# EEZ_DIB_BP3C_r3B3.net
KiCad netlist of a schematic drawn in EAGLE
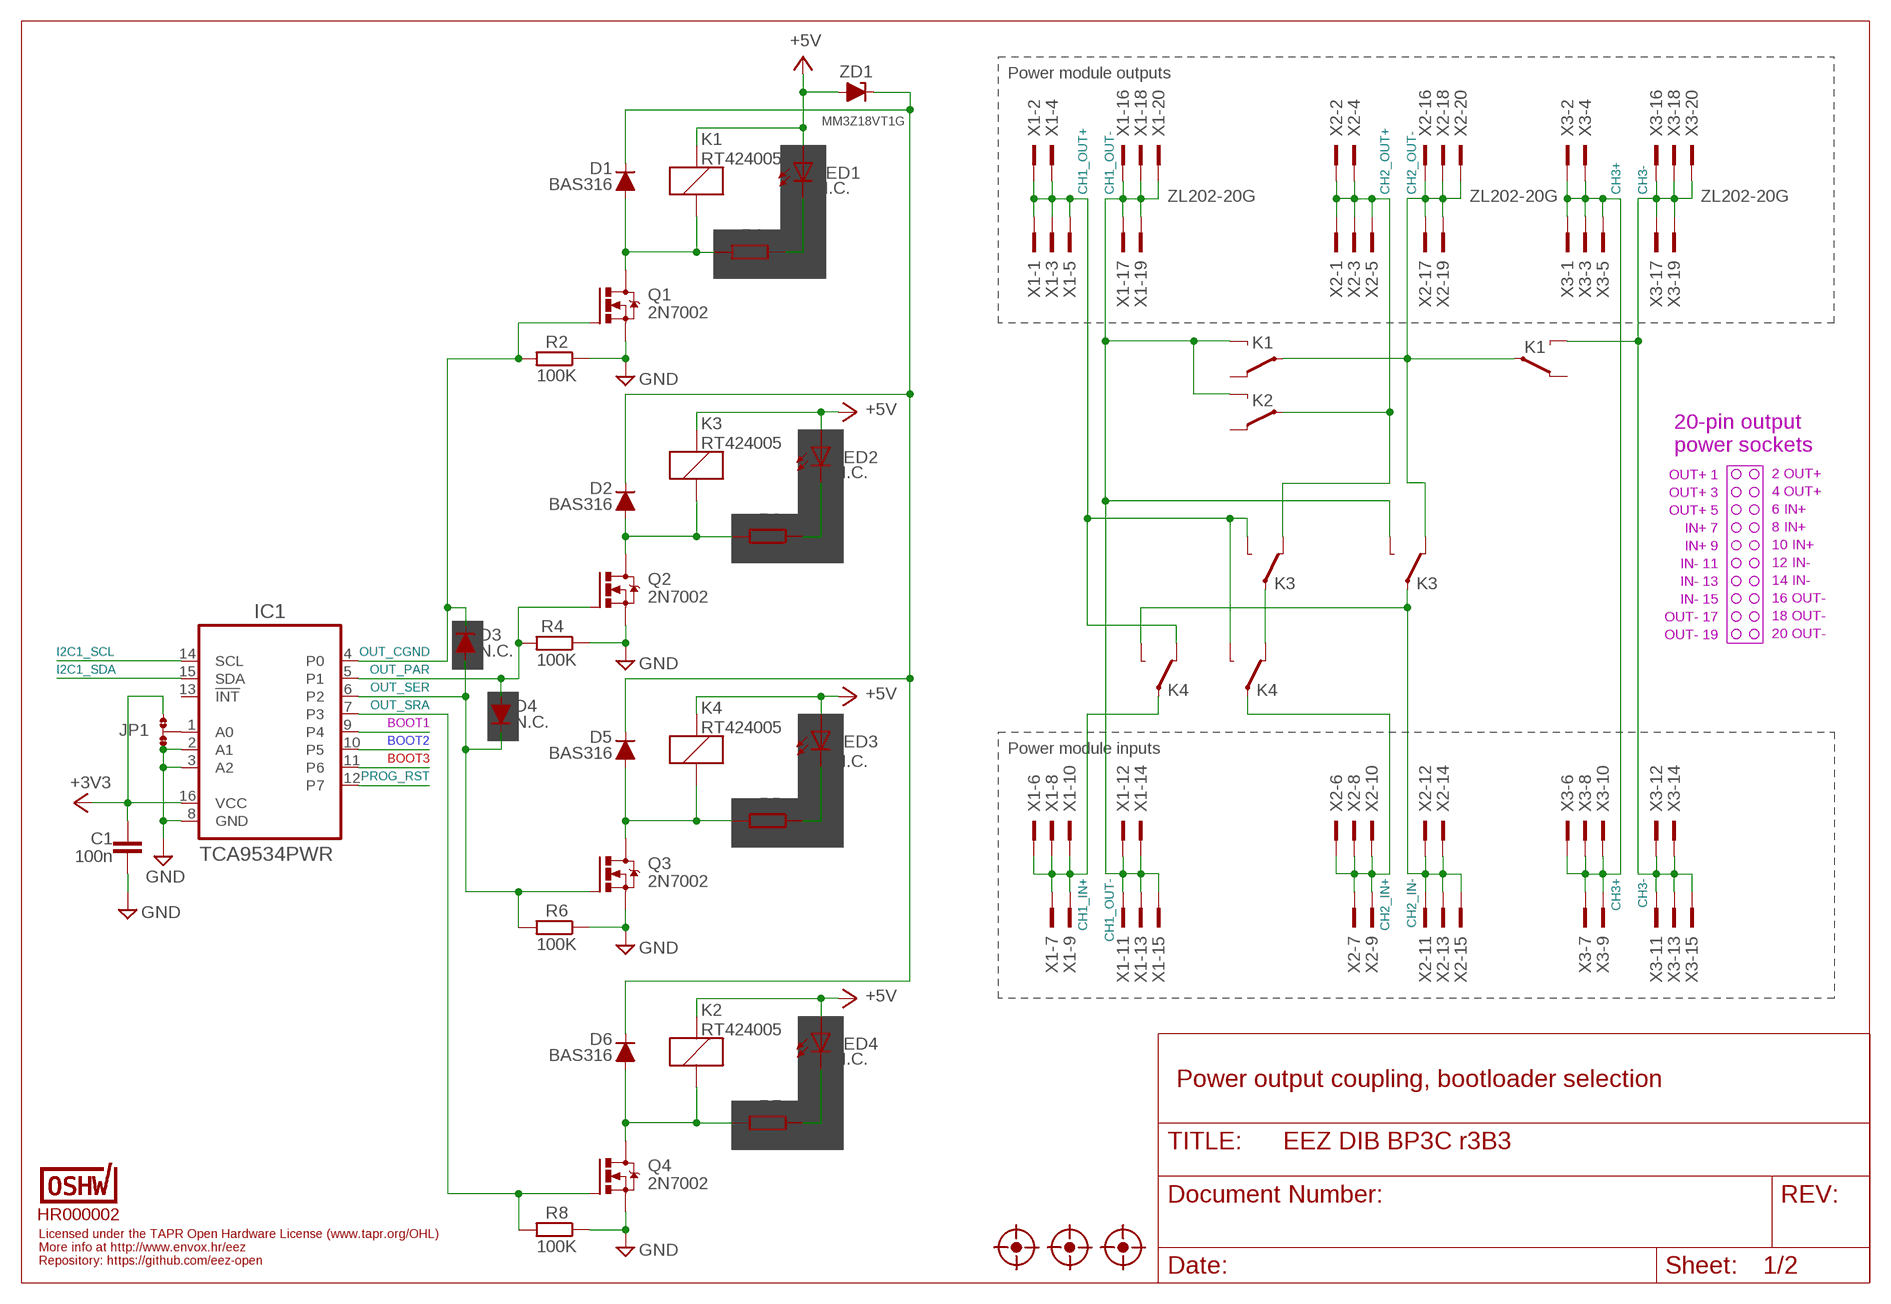
[diagram p0: schematic, sheet 1]
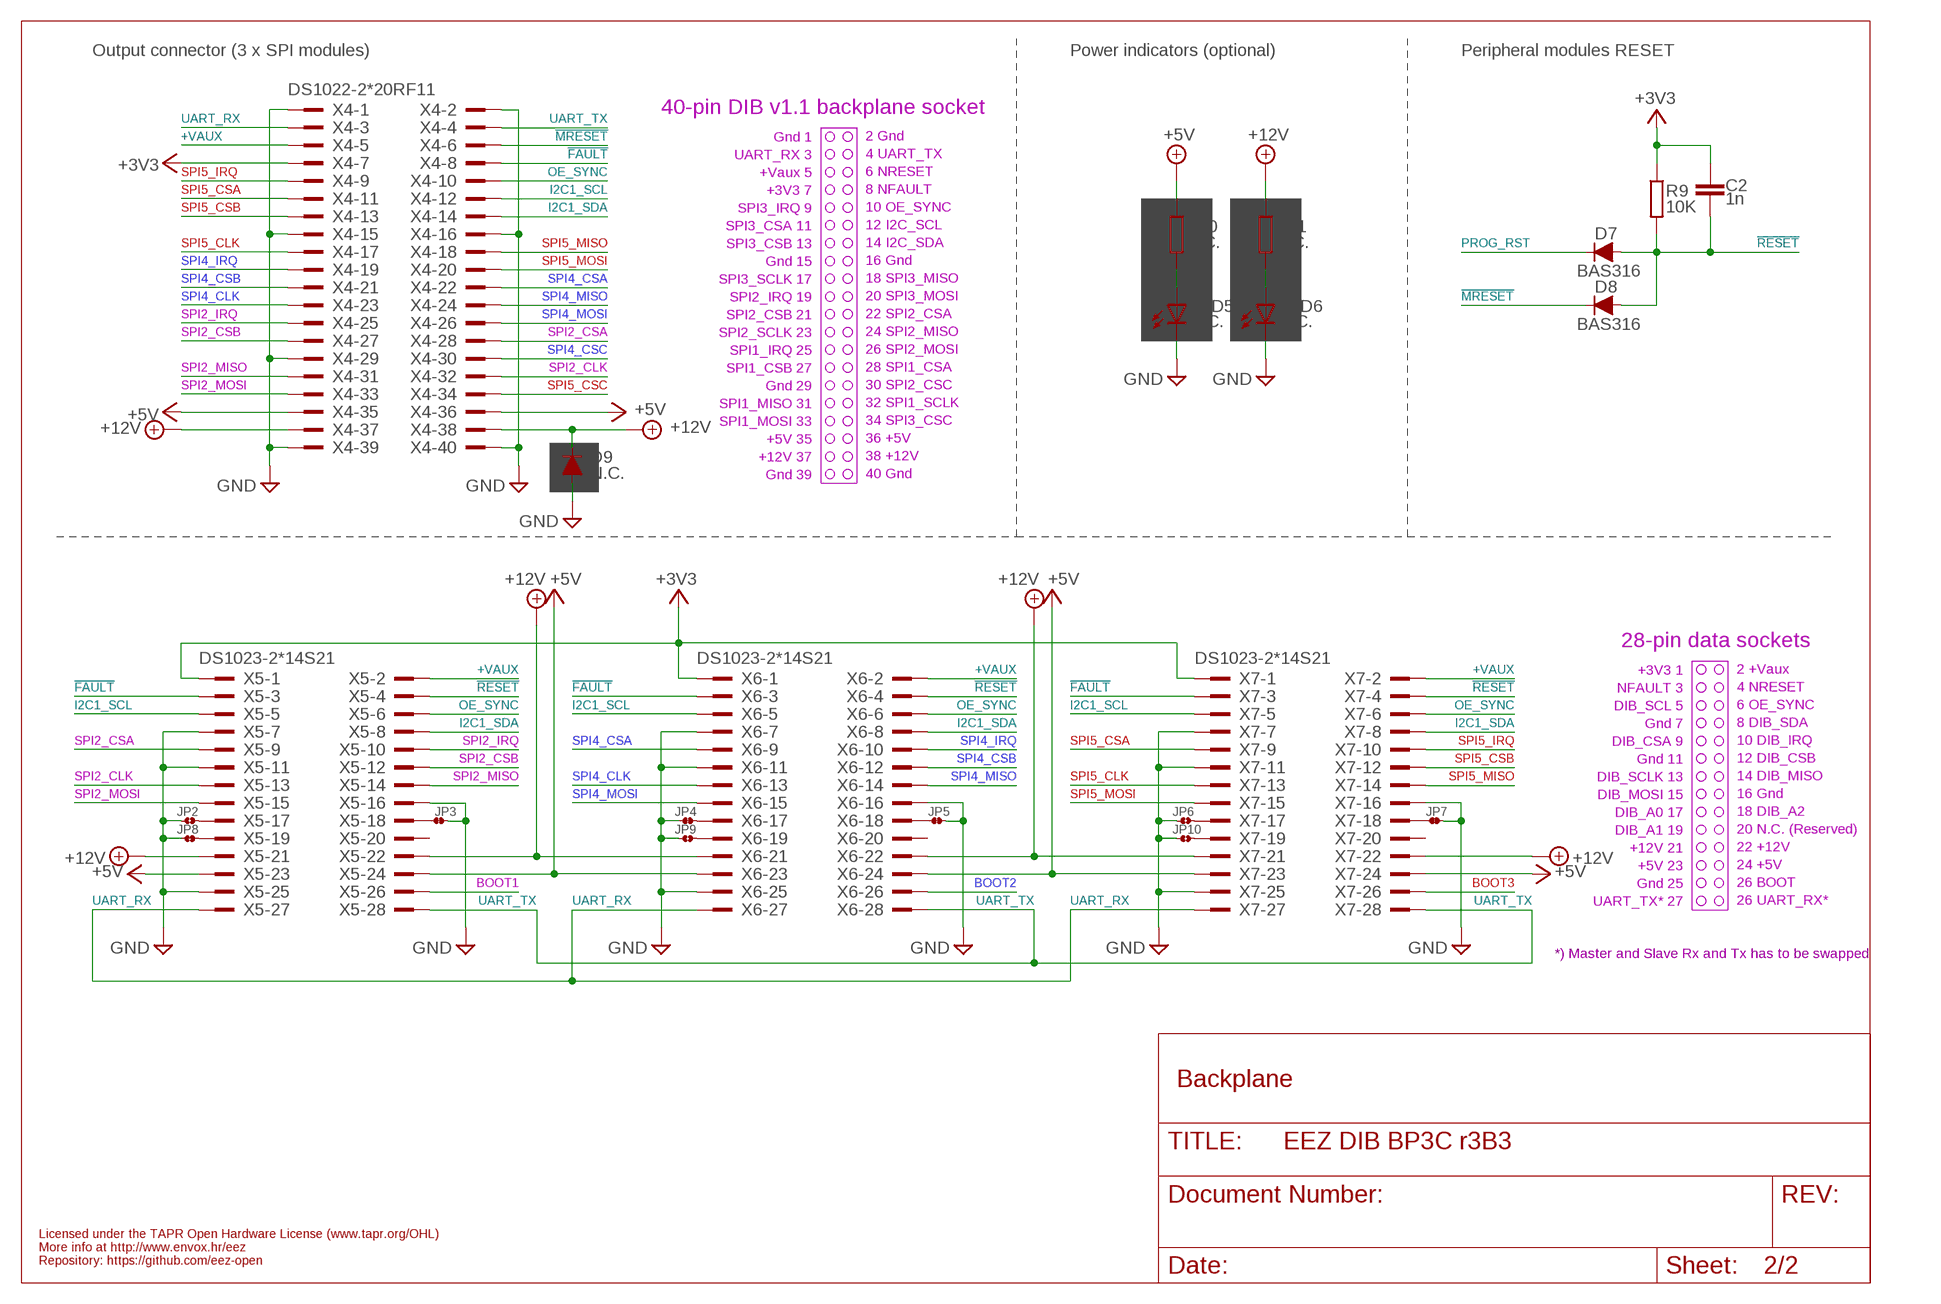
[diagram p1: schematic, sheet 2]

(export (version "E")
  (design (tool "Eeschema 10.0.6"))
  (components
    (comp (ref "C2")
      (value "1n")
      (footprint "eagle-import:C0805")
      (libsource (lib "eagle-import") (part "C-EUC0805"))
    )
    (comp (ref "D7")
      (value "BAS316")
      (footprint "eagle-import:SOD323-R")
      (libsource (lib "eagle-import") (part "DIODESOD323R"))
    )
    (comp (ref "D8")
      (value "BAS316")
      (footprint "eagle-import:SOD323-R")
      (libsource (lib "eagle-import") (part "DIODESOD323R"))
    )
    (comp (ref "D9")
      (value "N.C.")
      (footprint "eagle-import:DO214AA")
      (libsource (lib "eagle-import") (part "MyLib6_DIODEDO214AA"))
    )
    (comp (ref "JP2")
      (value "JP2-CUT")
      (footprint "eagle-import:JP2-CUT")
      (libsource (lib "eagle-import") (part "JP2-CUT"))
    )
    (comp (ref "JP3")
      (value "JP2-NOCUT")
      (footprint "eagle-import:JP2-NOCUT")
      (libsource (lib "eagle-import") (part "JP2-NOCUT"))
    )
    (comp (ref "JP4")
      (value "JP2-NOCUT")
      (footprint "eagle-import:JP2-NOCUT")
      (libsource (lib "eagle-import") (part "JP2-NOCUT"))
    )
    (comp (ref "JP5")
      (value "JP2-NOCUT")
      (footprint "eagle-import:JP2-NOCUT")
      (libsource (lib "eagle-import") (part "JP2-NOCUT"))
    )
    (comp (ref "JP6")
      (value "JP2-CUT")
      (footprint "eagle-import:JP2-CUT")
      (libsource (lib "eagle-import") (part "JP2-CUT"))
    )
    (comp (ref "JP7")
      (value "JP2-NOCUT")
      (footprint "eagle-import:JP2-NOCUT")
      (libsource (lib "eagle-import") (part "JP2-NOCUT"))
    )
    (comp (ref "JP8")
      (value "JP2-NOCUT")
      (footprint "eagle-import:JP2-NOCUT")
      (libsource (lib "eagle-import") (part "JP2-NOCUT"))
    )
    (comp (ref "JP9")
      (value "JP2-CUT")
      (footprint "eagle-import:JP2-CUT")
      (libsource (lib "eagle-import") (part "JP2-CUT"))
    )
    (comp (ref "JP10")
      (value "JP2-CUT")
      (footprint "eagle-import:JP2-CUT")
      (libsource (lib "eagle-import") (part "JP2-CUT"))
    )
    (comp (ref "LED5")
      (value "N.C.")
      (footprint "eagle-import:LED_0805")
      (libsource (lib "eagle-import") (part "LED0805"))
    )
    (comp (ref "LED6")
      (value "N.C.")
      (footprint "eagle-import:LED_0805")
      (libsource (lib "eagle-import") (part "LED0805"))
    )
    (comp (ref "R9")
      (value "10K")
      (footprint "eagle-import:R0805")
      (libsource (lib "eagle-import") (part "R-EU_R0805"))
    )
    (comp (ref "R10")
      (value "N.C.")
      (footprint "eagle-import:R0805")
      (libsource (lib "eagle-import") (part "R-EU_R0805"))
    )
    (comp (ref "R11")
      (value "N.C.")
      (footprint "eagle-import:R0805")
      (libsource (lib "eagle-import") (part "R-EU_R0805"))
    )
    (comp (ref "X4")
      (value "DS1022-2*20RF11")
      (footprint "eagle-import:ZL212-40KG")
      (libsource (lib "eagle-import") (part "ZL212-40KG"))
    )
    (comp (ref "X5")
      (value "DS1023-2*14S21")
      (footprint "eagle-import:TSW-114-07-F-D")
      (libsource (lib "eagle-import") (part "TSW-114-07-F-D"))
    )
    (comp (ref "X6")
      (value "DS1023-2*14S21")
      (footprint "eagle-import:TSW-114-07-F-D")
      (libsource (lib "eagle-import") (part "TSW-114-07-F-D"))
    )
    (comp (ref "X7")
      (value "DS1023-2*14S21")
      (footprint "eagle-import:TSW-114-07-F-D")
      (libsource (lib "eagle-import") (part "TSW-114-07-F-D"))
    )
    (comp (ref "C1")
      (value "100n")
      (footprint "eagle-import:C0603")
      (libsource (lib "eagle-import") (part "C-EUC0603"))
    )
    (comp (ref "D1")
      (value "BAS316")
      (footprint "eagle-import:SOD323-R")
      (libsource (lib "eagle-import") (part "DIODESOD323R"))
    )
    (comp (ref "D2")
      (value "BAS316")
      (footprint "eagle-import:SOD323-R")
      (libsource (lib "eagle-import") (part "DIODESOD323R"))
    )
    (comp (ref "D3")
      (value "N.C.")
      (footprint "eagle-import:SOD323-R")
      (libsource (lib "eagle-import") (part "DIODESOD323R"))
    )
    (comp (ref "D4")
      (value "N.C.")
      (footprint "eagle-import:SOD323-R")
      (libsource (lib "eagle-import") (part "DIODESOD323R"))
    )
    (comp (ref "D5")
      (value "BAS316")
      (footprint "eagle-import:SOD323-R")
      (libsource (lib "eagle-import") (part "DIODESOD323R"))
    )
    (comp (ref "D6")
      (value "BAS316")
      (footprint "eagle-import:SOD323-R")
      (libsource (lib "eagle-import") (part "DIODESOD323R"))
    )
    (comp (ref "FM1")
      (value "FIDUCIAL")
      (footprint "eagle-import:FIDUCIAL")
      (libsource (lib "eagle-import") (part "FIDUCIAL"))
    )
    (comp (ref "FM2")
      (value "FIDUCIAL")
      (footprint "eagle-import:FIDUCIAL")
      (libsource (lib "eagle-import") (part "FIDUCIAL"))
    )
    (comp (ref "FM3")
      (value "FIDUCIAL")
      (footprint "eagle-import:FIDUCIAL")
      (libsource (lib "eagle-import") (part "FIDUCIAL"))
    )
    (comp (ref "IC1")
      (value "TCA9534PWR")
      (footprint "eagle-import:PW(R-PDSO-G16)")
      (libsource (lib "eagle-import") (part "TCA9534PWR"))
    )
    (comp (ref "JP1")
      (value "JP3-CUT")
      (footprint "eagle-import:JP3-CUT")
      (libsource (lib "eagle-import") (part "JP3-CUT"))
    )
    (comp (ref "K1")
      (value "RT424005")
      (footprint "eagle-import:RT-C_016A5_ROUND")
      (libsource (lib "eagle-import") (part "RELAY_RT314012-2"))
    )
    (comp (ref "K2")
      (value "RT424005")
      (footprint "eagle-import:RT-C_016A5_ROUND")
      (libsource (lib "eagle-import") (part "RELAY_RT314012-2"))
    )
    (comp (ref "K3")
      (value "RT424005")
      (footprint "eagle-import:RT-C_016A5_ROUND")
      (libsource (lib "eagle-import") (part "RELAY_RT314012-2"))
    )
    (comp (ref "K4")
      (value "RT424005")
      (footprint "eagle-import:RT-C_016A5_ROUND")
      (libsource (lib "eagle-import") (part "RELAY_RT314012-2"))
    )
    (comp (ref "LABEL1")
      (value "HR000002")
      (footprint "eagle-import:CERT-SMALL-SILK")
      (libsource (lib "eagle-import") (part "OSHWA-CERT-SMALL"))
    )
    (comp (ref "LED1")
      (value "N.C.")
      (footprint "eagle-import:LED_0805")
      (libsource (lib "eagle-import") (part "LED0805"))
    )
    (comp (ref "LED2")
      (value "N.C.")
      (footprint "eagle-import:LED_0805")
      (libsource (lib "eagle-import") (part "LED0805"))
    )
    (comp (ref "LED3")
      (value "N.C.")
      (footprint "eagle-import:LED_0805")
      (libsource (lib "eagle-import") (part "LED0805"))
    )
    (comp (ref "LED4")
      (value "N.C.")
      (footprint "eagle-import:LED_0805")
      (libsource (lib "eagle-import") (part "LED0805"))
    )
    (comp (ref "Q1")
      (value "2N7002")
      (footprint "eagle-import:SOT103P240X110-3N")
      (fields
        (field (name "MPN") "2N7002-7-F")
        (field (name "MPN_1") "2N7002-7-F")
        (field (name "OC_FARNELL") "1713823")
        (field (name "OC_NEWARK") "25R5679")
        (field (name "PACKAGE") "SOT-23-3")
        (field (name "SUPPLIER") "DIODES INC.")
      )
      (libsource (lib "eagle-import") (part "2N7002"))
    )
    (comp (ref "Q2")
      (value "2N7002")
      (footprint "eagle-import:SOT103P240X110-3N")
      (fields
        (field (name "MPN") "2N7002-7-F")
        (field (name "MPN_1") "2N7002-7-F")
        (field (name "OC_FARNELL") "1713823")
        (field (name "OC_NEWARK") "25R5679")
        (field (name "PACKAGE") "SOT-23-3")
        (field (name "SUPPLIER") "DIODES INC.")
      )
      (libsource (lib "eagle-import") (part "2N7002"))
    )
    (comp (ref "Q3")
      (value "2N7002")
      (footprint "eagle-import:SOT103P240X110-3N")
      (fields
        (field (name "MPN") "2N7002-7-F")
        (field (name "MPN_1") "2N7002-7-F")
        (field (name "OC_FARNELL") "1713823")
        (field (name "OC_NEWARK") "25R5679")
        (field (name "PACKAGE") "SOT-23-3")
        (field (name "SUPPLIER") "DIODES INC.")
      )
      (libsource (lib "eagle-import") (part "2N7002"))
    )
    (comp (ref "Q4")
      (value "2N7002")
      (footprint "eagle-import:SOT103P240X110-3N")
      (fields
        (field (name "MPN") "2N7002-7-F")
        (field (name "MPN_1") "2N7002-7-F")
        (field (name "OC_FARNELL") "1713823")
        (field (name "OC_NEWARK") "25R5679")
        (field (name "PACKAGE") "SOT-23-3")
        (field (name "SUPPLIER") "DIODES INC.")
      )
      (libsource (lib "eagle-import") (part "2N7002"))
    )
    (comp (ref "R1")
      (value "N.C.")
      (footprint "eagle-import:R0805")
      (libsource (lib "eagle-import") (part "R-EU_R0805"))
    )
    (comp (ref "R2")
      (value "100K")
      (footprint "eagle-import:R0805")
      (libsource (lib "eagle-import") (part "R-EU_R0805"))
    )
    (comp (ref "R3")
      (value "N.C.")
      (footprint "eagle-import:R0805")
      (libsource (lib "eagle-import") (part "R-EU_R0805"))
    )
    (comp (ref "R4")
      (value "100K")
      (footprint "eagle-import:R0805")
      (libsource (lib "eagle-import") (part "R-EU_R0805"))
    )
    (comp (ref "R5")
      (value "N.C.")
      (footprint "eagle-import:R0805")
      (libsource (lib "eagle-import") (part "R-EU_R0805"))
    )
    (comp (ref "R6")
      (value "100K")
      (footprint "eagle-import:R0805")
      (libsource (lib "eagle-import") (part "R-EU_R0805"))
    )
    (comp (ref "R7")
      (value "N.C.")
      (footprint "eagle-import:R0805")
      (libsource (lib "eagle-import") (part "R-EU_R0805"))
    )
    (comp (ref "R8")
      (value "100K")
      (footprint "eagle-import:R0805")
      (libsource (lib "eagle-import") (part "R-EU_R0805"))
    )
    (comp (ref "X1")
      (value "ZL202-20G")
      (footprint "eagle-import:DS1021-2_10SF11")
      (libsource (lib "eagle-import") (part "DS1021-210SF11"))
    )
    (comp (ref "X2")
      (value "ZL202-20G")
      (footprint "eagle-import:DS1021-2_10SF11")
      (libsource (lib "eagle-import") (part "DS1021-210SF11"))
    )
    (comp (ref "X3")
      (value "ZL202-20G")
      (footprint "eagle-import:DS1021-2_10SF11")
      (libsource (lib "eagle-import") (part "DS1021-210SF11"))
    )
    (comp (ref "ZD1")
      (value "MM3Z18VT1G")
      (footprint "eagle-import:SOD323-R")
      (libsource (lib "eagle-import") (part "ZENER-DIODESOD323R"))
    )
  )
  (nets
    (net (code "1") (name "+3V3") (class "Default")
      (node (ref "C1") (pin "1") (pinfunction "1_1") (pintype "passive"))
      (node (ref "C2") (pin "2") (pinfunction "2_2") (pintype "passive"))
      (node (ref "IC1") (pin "16") (pinfunction "VCC_16") (pintype "passive"))
      (node (ref "JP1") (pin "NO") (pinfunction "NO_NO") (pintype "passive"))
      (node (ref "R9") (pin "1") (pinfunction "1_1") (pintype "passive"))
      (node (ref "X4") (pin "7") (pinfunction "1_7") (pintype "passive"))
      (node (ref "X5") (pin "1") (pinfunction "1_1") (pintype "passive"))
      (node (ref "X6") (pin "1") (pinfunction "1_1") (pintype "passive"))
      (node (ref "X7") (pin "1") (pinfunction "1_1") (pintype "passive"))
    )
    (net (code "2") (name "+5V") (class "Default")
      (node (ref "K1") (pin "A2") (pinfunction "C1_A2") (pintype "passive"))
      (node (ref "K2") (pin "A2") (pinfunction "C1_A2") (pintype "passive"))
      (node (ref "K3") (pin "A2") (pinfunction "C1_A2") (pintype "passive"))
      (node (ref "K4") (pin "A2") (pinfunction "C1_A2") (pintype "passive"))
      (node (ref "LED1") (pin "A") (pinfunction "A_A") (pintype "passive"))
      (node (ref "LED2") (pin "A") (pinfunction "A_A") (pintype "passive"))
      (node (ref "LED3") (pin "A") (pinfunction "A_A") (pintype "passive"))
      (node (ref "LED4") (pin "A") (pinfunction "A_A") (pintype "passive"))
      (node (ref "R10") (pin "1") (pinfunction "1_1") (pintype "passive"))
      (node (ref "X4") (pin "35") (pinfunction "1_35") (pintype "passive"))
      (node (ref "X4") (pin "36") (pinfunction "1_36") (pintype "passive"))
      (node (ref "X5") (pin "23") (pinfunction "1_23") (pintype "passive"))
      (node (ref "X5") (pin "24") (pinfunction "1_24") (pintype "passive"))
      (node (ref "X6") (pin "23") (pinfunction "1_23") (pintype "passive"))
      (node (ref "X6") (pin "24") (pinfunction "1_24") (pintype "passive"))
      (node (ref "X7") (pin "23") (pinfunction "1_23") (pintype "passive"))
      (node (ref "X7") (pin "24") (pinfunction "1_24") (pintype "passive"))
      (node (ref "ZD1") (pin "A") (pinfunction "A_A") (pintype "passive"))
    )
    (net (code "3") (name "+12V") (class "Default")
      (node (ref "D9") (pin "C") (pinfunction "C_C") (pintype "passive"))
      (node (ref "R11") (pin "1") (pinfunction "1_1") (pintype "passive"))
      (node (ref "X4") (pin "37") (pinfunction "1_37") (pintype "passive"))
      (node (ref "X4") (pin "38") (pinfunction "1_38") (pintype "passive"))
      (node (ref "X5") (pin "21") (pinfunction "1_21") (pintype "passive"))
      (node (ref "X5") (pin "22") (pinfunction "1_22") (pintype "passive"))
      (node (ref "X6") (pin "21") (pinfunction "1_21") (pintype "passive"))
      (node (ref "X6") (pin "22") (pinfunction "1_22") (pintype "passive"))
      (node (ref "X7") (pin "21") (pinfunction "1_21") (pintype "passive"))
      (node (ref "X7") (pin "22") (pinfunction "1_22") (pintype "passive"))
    )
    (net (code "4") (name "+VAUX") (class "Default")
      (node (ref "X4") (pin "5") (pinfunction "1_5") (pintype "passive"))
      (node (ref "X5") (pin "2") (pinfunction "1_2") (pintype "passive"))
      (node (ref "X6") (pin "2") (pinfunction "1_2") (pintype "passive"))
      (node (ref "X7") (pin "2") (pinfunction "1_2") (pintype "passive"))
    )
    (net (code "5") (name "BOOT1") (class "Default")
      (node (ref "IC1") (pin "9") (pinfunction "P4_9") (pintype "bidirectional"))
      (node (ref "X5") (pin "26") (pinfunction "1_26") (pintype "passive"))
    )
    (net (code "6") (name "BOOT2") (class "Default")
      (node (ref "IC1") (pin "10") (pinfunction "P5_10") (pintype "bidirectional"))
      (node (ref "X6") (pin "26") (pinfunction "1_26") (pintype "passive"))
    )
    (net (code "7") (name "BOOT3") (class "Default")
      (node (ref "IC1") (pin "11") (pinfunction "P6_11") (pintype "bidirectional"))
      (node (ref "X7") (pin "26") (pinfunction "1_26") (pintype "passive"))
    )
    (net (code "8") (name "CH1_IN+") (class "Default")
      (node (ref "K4") (pin "11A") (pinfunction "P_11A") (pintype "passive"))
      (node (ref "X1") (pin "10") (pinfunction "1_10") (pintype "passive"))
      (node (ref "X1") (pin "6") (pinfunction "1_6") (pintype "passive"))
      (node (ref "X1") (pin "7") (pinfunction "1_7") (pintype "passive"))
      (node (ref "X1") (pin "8") (pinfunction "1_8") (pintype "passive"))
      (node (ref "X1") (pin "9") (pinfunction "1_9") (pintype "passive"))
    )
    (net (code "9") (name "CH1_OUT+") (class "Default")
      (node (ref "K3") (pin "14A") (pinfunction "O_14A") (pintype "passive"))
      (node (ref "K4") (pin "12A") (pinfunction "S_12A") (pintype "passive"))
      (node (ref "K4") (pin "14B") (pinfunction "O_14B") (pintype "passive"))
      (node (ref "X1") (pin "1") (pinfunction "1_1") (pintype "passive"))
      (node (ref "X1") (pin "2") (pinfunction "1_2") (pintype "passive"))
      (node (ref "X1") (pin "3") (pinfunction "1_3") (pintype "passive"))
      (node (ref "X1") (pin "4") (pinfunction "1_4") (pintype "passive"))
      (node (ref "X1") (pin "5") (pinfunction "1_5") (pintype "passive"))
    )
    (net (code "10") (name "CH1_OUT-") (class "Default")
      (node (ref "K1") (pin "14A") (pinfunction "O_14A") (pintype "passive"))
      (node (ref "K2") (pin "14A") (pinfunction "O_14A") (pintype "passive"))
      (node (ref "K3") (pin "14B") (pinfunction "O_14B") (pintype "passive"))
      (node (ref "X1") (pin "11") (pinfunction "1_11") (pintype "passive"))
      (node (ref "X1") (pin "12") (pinfunction "1_12") (pintype "passive"))
      (node (ref "X1") (pin "13") (pinfunction "1_13") (pintype "passive"))
      (node (ref "X1") (pin "14") (pinfunction "1_14") (pintype "passive"))
      (node (ref "X1") (pin "15") (pinfunction "1_15") (pintype "passive"))
      (node (ref "X1") (pin "16") (pinfunction "1_16") (pintype "passive"))
      (node (ref "X1") (pin "17") (pinfunction "1_17") (pintype "passive"))
      (node (ref "X1") (pin "18") (pinfunction "1_18") (pintype "passive"))
      (node (ref "X1") (pin "19") (pinfunction "1_19") (pintype "passive"))
      (node (ref "X1") (pin "20") (pinfunction "1_20") (pintype "passive"))
    )
    (net (code "11") (name "CH2_IN+") (class "Default")
      (node (ref "K4") (pin "11B") (pinfunction "P_11B") (pintype "passive"))
      (node (ref "X2") (pin "10") (pinfunction "1_10") (pintype "passive"))
      (node (ref "X2") (pin "6") (pinfunction "1_6") (pintype "passive"))
      (node (ref "X2") (pin "7") (pinfunction "1_7") (pintype "passive"))
      (node (ref "X2") (pin "8") (pinfunction "1_8") (pintype "passive"))
      (node (ref "X2") (pin "9") (pinfunction "1_9") (pintype "passive"))
    )
    (net (code "12") (name "CH2_IN-") (class "Default")
      (node (ref "K3") (pin "11B") (pinfunction "P_11B") (pintype "passive"))
      (node (ref "K4") (pin "14A") (pinfunction "O_14A") (pintype "passive"))
      (node (ref "X2") (pin "11") (pinfunction "1_11") (pintype "passive"))
      (node (ref "X2") (pin "12") (pinfunction "1_12") (pintype "passive"))
      (node (ref "X2") (pin "13") (pinfunction "1_13") (pintype "passive"))
      (node (ref "X2") (pin "14") (pinfunction "1_14") (pintype "passive"))
      (node (ref "X2") (pin "15") (pinfunction "1_15") (pintype "passive"))
    )
    (net (code "13") (name "CH2_OUT+") (class "Default")
      (node (ref "K2") (pin "11A") (pinfunction "P_11A") (pintype "passive"))
      (node (ref "K3") (pin "12A") (pinfunction "S_12A") (pintype "passive"))
      (node (ref "X2") (pin "1") (pinfunction "1_1") (pintype "passive"))
      (node (ref "X2") (pin "2") (pinfunction "1_2") (pintype "passive"))
      (node (ref "X2") (pin "3") (pinfunction "1_3") (pintype "passive"))
      (node (ref "X2") (pin "4") (pinfunction "1_4") (pintype "passive"))
      (node (ref "X2") (pin "5") (pinfunction "1_5") (pintype "passive"))
    )
    (net (code "14") (name "CH2_OUT-") (class "Default")
      (node (ref "K1") (pin "11A") (pinfunction "P_11A") (pintype "passive"))
      (node (ref "K1") (pin "11B") (pinfunction "P_11B") (pintype "passive"))
      (node (ref "K3") (pin "12B") (pinfunction "S_12B") (pintype "passive"))
      (node (ref "X2") (pin "16") (pinfunction "1_16") (pintype "passive"))
      (node (ref "X2") (pin "17") (pinfunction "1_17") (pintype "passive"))
      (node (ref "X2") (pin "18") (pinfunction "1_18") (pintype "passive"))
      (node (ref "X2") (pin "19") (pinfunction "1_19") (pintype "passive"))
      (node (ref "X2") (pin "20") (pinfunction "1_20") (pintype "passive"))
    )
    (net (code "15") (name "CH3+") (class "Default")
      (node (ref "X3") (pin "1") (pinfunction "1_1") (pintype "passive"))
      (node (ref "X3") (pin "10") (pinfunction "1_10") (pintype "passive"))
      (node (ref "X3") (pin "2") (pinfunction "1_2") (pintype "passive"))
      (node (ref "X3") (pin "3") (pinfunction "1_3") (pintype "passive"))
      (node (ref "X3") (pin "4") (pinfunction "1_4") (pintype "passive"))
      (node (ref "X3") (pin "5") (pinfunction "1_5") (pintype "passive"))
      (node (ref "X3") (pin "6") (pinfunction "1_6") (pintype "passive"))
      (node (ref "X3") (pin "7") (pinfunction "1_7") (pintype "passive"))
      (node (ref "X3") (pin "8") (pinfunction "1_8") (pintype "passive"))
      (node (ref "X3") (pin "9") (pinfunction "1_9") (pintype "passive"))
    )
    (net (code "16") (name "CH3-") (class "Default")
      (node (ref "K1") (pin "14B") (pinfunction "O_14B") (pintype "passive"))
      (node (ref "X3") (pin "11") (pinfunction "1_11") (pintype "passive"))
      (node (ref "X3") (pin "12") (pinfunction "1_12") (pintype "passive"))
      (node (ref "X3") (pin "13") (pinfunction "1_13") (pintype "passive"))
      (node (ref "X3") (pin "14") (pinfunction "1_14") (pintype "passive"))
      (node (ref "X3") (pin "15") (pinfunction "1_15") (pintype "passive"))
      (node (ref "X3") (pin "16") (pinfunction "1_16") (pintype "passive"))
      (node (ref "X3") (pin "17") (pinfunction "1_17") (pintype "passive"))
      (node (ref "X3") (pin "18") (pinfunction "1_18") (pintype "passive"))
      (node (ref "X3") (pin "19") (pinfunction "1_19") (pintype "passive"))
      (node (ref "X3") (pin "20") (pinfunction "1_20") (pintype "passive"))
    )
    (net (code "17") (name "GND") (class "Default")
      (node (ref "C1") (pin "2") (pinfunction "2_2") (pintype "passive"))
      (node (ref "D9") (pin "A") (pinfunction "A_A") (pintype "passive"))
      (node (ref "IC1") (pin "2") (pinfunction "A1_2") (pintype "input"))
      (node (ref "IC1") (pin "3") (pinfunction "A2_3") (pintype "input"))
      (node (ref "IC1") (pin "8") (pinfunction "GND_8") (pintype "passive"))
      (node (ref "JP1") (pin "NC") (pinfunction "NC_NC") (pintype "passive"))
      (node (ref "JP10") (pin "1") (pinfunction "1_1") (pintype "passive"))
      (node (ref "JP2") (pin "1") (pinfunction "1_1") (pintype "passive"))
      (node (ref "JP3") (pin "2") (pinfunction "2_2") (pintype "passive"))
      (node (ref "JP4") (pin "1") (pinfunction "1_1") (pintype "passive"))
      (node (ref "JP5") (pin "2") (pinfunction "2_2") (pintype "passive"))
      (node (ref "JP6") (pin "1") (pinfunction "1_1") (pintype "passive"))
      (node (ref "JP7") (pin "2") (pinfunction "2_2") (pintype "passive"))
      (node (ref "JP8") (pin "1") (pinfunction "1_1") (pintype "passive"))
      (node (ref "JP9") (pin "1") (pinfunction "1_1") (pintype "passive"))
      (node (ref "LED5") (pin "C") (pinfunction "C_C") (pintype "passive"))
      (node (ref "LED6") (pin "C") (pinfunction "C_C") (pintype "passive"))
      (node (ref "Q1") (pin "2") (pinfunction "S_2") (pintype "passive"))
      (node (ref "Q2") (pin "2") (pinfunction "S_2") (pintype "passive"))
      (node (ref "Q3") (pin "2") (pinfunction "S_2") (pintype "passive"))
      (node (ref "Q4") (pin "2") (pinfunction "S_2") (pintype "passive"))
      (node (ref "R2") (pin "1") (pinfunction "1_1") (pintype "passive"))
      (node (ref "R4") (pin "1") (pinfunction "1_1") (pintype "passive"))
      (node (ref "R6") (pin "1") (pinfunction "1_1") (pintype "passive"))
      (node (ref "R8") (pin "1") (pinfunction "1_1") (pintype "passive"))
      (node (ref "X4") (pin "1") (pinfunction "1_1") (pintype "passive"))
      (node (ref "X4") (pin "15") (pinfunction "1_15") (pintype "passive"))
      (node (ref "X4") (pin "16") (pinfunction "1_16") (pintype "passive"))
      (node (ref "X4") (pin "2") (pinfunction "1_2") (pintype "passive"))
      (node (ref "X4") (pin "29") (pinfunction "1_29") (pintype "passive"))
      (node (ref "X4") (pin "39") (pinfunction "1_39") (pintype "passive"))
      (node (ref "X4") (pin "40") (pinfunction "1_40") (pintype "passive"))
      (node (ref "X5") (pin "11") (pinfunction "1_11") (pintype "passive"))
      (node (ref "X5") (pin "16") (pinfunction "1_16") (pintype "passive"))
      (node (ref "X5") (pin "25") (pinfunction "1_25") (pintype "passive"))
      (node (ref "X5") (pin "7") (pinfunction "1_7") (pintype "passive"))
      (node (ref "X6") (pin "11") (pinfunction "1_11") (pintype "passive"))
      (node (ref "X6") (pin "16") (pinfunction "1_16") (pintype "passive"))
      (node (ref "X6") (pin "25") (pinfunction "1_25") (pintype "passive"))
      (node (ref "X6") (pin "7") (pinfunction "1_7") (pintype "passive"))
      (node (ref "X7") (pin "11") (pinfunction "1_11") (pintype "passive"))
      (node (ref "X7") (pin "16") (pinfunction "1_16") (pintype "passive"))
      (node (ref "X7") (pin "25") (pinfunction "1_25") (pintype "passive"))
      (node (ref "X7") (pin "7") (pinfunction "1_7") (pintype "passive"))
    )
    (net (code "18") (name "I2C1_SCL") (class "Default")
      (node (ref "IC1") (pin "14") (pinfunction "SCL_14") (pintype "input"))
      (node (ref "X4") (pin "12") (pinfunction "1_12") (pintype "passive"))
      (node (ref "X5") (pin "5") (pinfunction "1_5") (pintype "passive"))
      (node (ref "X6") (pin "5") (pinfunction "1_5") (pintype "passive"))
      (node (ref "X7") (pin "5") (pinfunction "1_5") (pintype "passive"))
    )
    (net (code "19") (name "I2C1_SDA") (class "Default")
      (node (ref "IC1") (pin "15") (pinfunction "SDA_15") (pintype "bidirectional"))
      (node (ref "X4") (pin "14") (pinfunction "1_14") (pintype "passive"))
      (node (ref "X5") (pin "8") (pinfunction "1_8") (pintype "passive"))
      (node (ref "X6") (pin "8") (pinfunction "1_8") (pintype "passive"))
      (node (ref "X7") (pin "8") (pinfunction "1_8") (pintype "passive"))
    )
    (net (code "20") (name "Net-(D1-PadC)") (class "Default")
      (node (ref "D1") (pin "C") (pinfunction "C_C") (pintype "passive"))
      (node (ref "D2") (pin "C") (pinfunction "C_C") (pintype "passive"))
      (node (ref "D5") (pin "C") (pinfunction "C_C") (pintype "passive"))
      (node (ref "D6") (pin "C") (pinfunction "C_C") (pintype "passive"))
      (node (ref "ZD1") (pin "C") (pinfunction "C_C") (pintype "passive"))
    )
    (net (code "21") (name "Net-(IC1-A0)") (class "Default")
      (node (ref "IC1") (pin "1") (pinfunction "A0_1") (pintype "input"))
      (node (ref "JP1") (pin "COM") (pinfunction "COM_COM") (pintype "passive"))
    )
    (net (code "22") (name "Net-(K1C-C2)") (class "Default")
      (node (ref "D1") (pin "A") (pinfunction "A_A") (pintype "passive"))
      (node (ref "K1") (pin "A1") (pinfunction "C2_A1") (pintype "passive"))
      (node (ref "Q1") (pin "3") (pinfunction "D_3") (pintype "passive"))
      (node (ref "R1") (pin "2") (pinfunction "2_2") (pintype "passive"))
    )
    (net (code "23") (name "Net-(K2C-C2)") (class "Default")
      (node (ref "D6") (pin "A") (pinfunction "A_A") (pintype "passive"))
      (node (ref "K2") (pin "A1") (pinfunction "C2_A1") (pintype "passive"))
      (node (ref "Q4") (pin "3") (pinfunction "D_3") (pintype "passive"))
      (node (ref "R7") (pin "2") (pinfunction "2_2") (pintype "passive"))
    )
    (net (code "24") (name "Net-(K3A-P)") (class "Default")
      (node (ref "K3") (pin "11A") (pinfunction "P_11A") (pintype "passive"))
      (node (ref "K4") (pin "12B") (pinfunction "S_12B") (pintype "passive"))
    )
    (net (code "25") (name "Net-(K3C-C2)") (class "Default")
      (node (ref "D2") (pin "A") (pinfunction "A_A") (pintype "passive"))
      (node (ref "K3") (pin "A1") (pinfunction "C2_A1") (pintype "passive"))
      (node (ref "Q2") (pin "3") (pinfunction "D_3") (pintype "passive"))
      (node (ref "R3") (pin "2") (pinfunction "2_2") (pintype "passive"))
    )
    (net (code "26") (name "Net-(K4C-C2)") (class "Default")
      (node (ref "D5") (pin "A") (pinfunction "A_A") (pintype "passive"))
      (node (ref "K4") (pin "A1") (pinfunction "C2_A1") (pintype "passive"))
      (node (ref "Q3") (pin "3") (pinfunction "D_3") (pintype "passive"))
      (node (ref "R5") (pin "2") (pinfunction "2_2") (pintype "passive"))
    )
    (net (code "27") (name "Net-(LED1-PadC)") (class "Default")
      (node (ref "LED1") (pin "C") (pinfunction "C_C") (pintype "passive"))
      (node (ref "R1") (pin "1") (pinfunction "1_1") (pintype "passive"))
    )
    (net (code "28") (name "Net-(LED2-PadC)") (class "Default")
      (node (ref "LED2") (pin "C") (pinfunction "C_C") (pintype "passive"))
      (node (ref "R3") (pin "1") (pinfunction "1_1") (pintype "passive"))
    )
    (net (code "29") (name "Net-(LED3-PadC)") (class "Default")
      (node (ref "LED3") (pin "C") (pinfunction "C_C") (pintype "passive"))
      (node (ref "R5") (pin "1") (pinfunction "1_1") (pintype "passive"))
    )
    (net (code "30") (name "Net-(LED4-PadC)") (class "Default")
      (node (ref "LED4") (pin "C") (pinfunction "C_C") (pintype "passive"))
      (node (ref "R7") (pin "1") (pinfunction "1_1") (pintype "passive"))
    )
    (net (code "31") (name "Net-(LED5-PadA)") (class "Default")
      (node (ref "LED5") (pin "A") (pinfunction "A_A") (pintype "passive"))
      (node (ref "R10") (pin "2") (pinfunction "2_2") (pintype "passive"))
    )
    (net (code "32") (name "Net-(LED6-PadA)") (class "Default")
      (node (ref "LED6") (pin "A") (pinfunction "A_A") (pintype "passive"))
      (node (ref "R11") (pin "2") (pinfunction "2_2") (pintype "passive"))
    )
    (net (code "33") (name "Net-(X5I-1)") (class "Default")
      (node (ref "JP2") (pin "2") (pinfunction "2_2") (pintype "passive"))
      (node (ref "X5") (pin "17") (pinfunction "1_17") (pintype "passive"))
    )
    (net (code "34") (name "Net-(X5J-1)") (class "Default")
      (node (ref "JP3") (pin "1") (pinfunction "1_1") (pintype "passive"))
      (node (ref "X5") (pin "18") (pinfunction "1_18") (pintype "passive"))
    )
    (net (code "35") (name "Net-(X5K-1)") (class "Default")
      (node (ref "JP8") (pin "2") (pinfunction "2_2") (pintype "passive"))
      (node (ref "X5") (pin "19") (pinfunction "1_19") (pintype "passive"))
    )
    (net (code "36") (name "Net-(X6I-1)") (class "Default")
      (node (ref "JP4") (pin "2") (pinfunction "2_2") (pintype "passive"))
      (node (ref "X6") (pin "17") (pinfunction "1_17") (pintype "passive"))
    )
    (net (code "37") (name "Net-(X6J-1)") (class "Default")
      (node (ref "JP5") (pin "1") (pinfunction "1_1") (pintype "passive"))
      (node (ref "X6") (pin "18") (pinfunction "1_18") (pintype "passive"))
    )
    (net (code "38") (name "Net-(X6K-1)") (class "Default")
      (node (ref "JP9") (pin "2") (pinfunction "2_2") (pintype "passive"))
      (node (ref "X6") (pin "19") (pinfunction "1_19") (pintype "passive"))
    )
    (net (code "39") (name "Net-(X7I-1)") (class "Default")
      (node (ref "JP6") (pin "2") (pinfunction "2_2") (pintype "passive"))
      (node (ref "X7") (pin "17") (pinfunction "1_17") (pintype "passive"))
    )
    (net (code "40") (name "Net-(X7J-1)") (class "Default")
      (node (ref "JP7") (pin "1") (pinfunction "1_1") (pintype "passive"))
      (node (ref "X7") (pin "18") (pinfunction "1_18") (pintype "passive"))
    )
    (net (code "41") (name "Net-(X7K-1)") (class "Default")
      (node (ref "JP10") (pin "2") (pinfunction "2_2") (pintype "passive"))
      (node (ref "X7") (pin "19") (pinfunction "1_19") (pintype "passive"))
    )
    (net (code "42") (name "OE_SYNC") (class "Default")
      (node (ref "X4") (pin "10") (pinfunction "1_10") (pintype "passive"))
      (node (ref "X5") (pin "6") (pinfunction "1_6") (pintype "passive"))
      (node (ref "X6") (pin "6") (pinfunction "1_6") (pintype "passive"))
      (node (ref "X7") (pin "6") (pinfunction "1_6") (pintype "passive"))
    )
    (net (code "43") (name "OUT_CGND") (class "Default")
      (node (ref "D3") (pin "C") (pinfunction "C_C") (pintype "passive"))
      (node (ref "IC1") (pin "4") (pinfunction "P0_4") (pintype "bidirectional"))
      (node (ref "Q1") (pin "1") (pinfunction "G_1") (pintype "passive"))
      (node (ref "R2") (pin "2") (pinfunction "2_2") (pintype "passive"))
    )
    (net (code "44") (name "OUT_PAR") (class "Default")
      (node (ref "D4") (pin "A") (pinfunction "A_A") (pintype "passive"))
      (node (ref "IC1") (pin "5") (pinfunction "P1_5") (pintype "bidirectional"))
      (node (ref "Q2") (pin "1") (pinfunction "G_1") (pintype "passive"))
      (node (ref "R4") (pin "2") (pinfunction "2_2") (pintype "passive"))
    )
    (net (code "45") (name "OUT_SER") (class "Default")
      (node (ref "D3") (pin "A") (pinfunction "A_A") (pintype "passive"))
      (node (ref "D4") (pin "C") (pinfunction "C_C") (pintype "passive"))
      (node (ref "IC1") (pin "6") (pinfunction "P2_6") (pintype "bidirectional"))
      (node (ref "Q3") (pin "1") (pinfunction "G_1") (pintype "passive"))
      (node (ref "R6") (pin "2") (pinfunction "2_2") (pintype "passive"))
    )
    (net (code "46") (name "OUT_SRA") (class "Default")
      (node (ref "IC1") (pin "7") (pinfunction "P3_7") (pintype "bidirectional"))
      (node (ref "Q4") (pin "1") (pinfunction "G_1") (pintype "passive"))
      (node (ref "R8") (pin "2") (pinfunction "2_2") (pintype "passive"))
    )
    (net (code "47") (name "PROG_RST") (class "Default")
      (node (ref "D7") (pin "C") (pinfunction "C_C") (pintype "passive"))
      (node (ref "IC1") (pin "12") (pinfunction "P7_12") (pintype "bidirectional"))
    )
    (net (code "48") (name "SPI2_CLK") (class "Default")
      (node (ref "X4") (pin "32") (pinfunction "1_32") (pintype "passive"))
      (node (ref "X5") (pin "13") (pinfunction "1_13") (pintype "passive"))
    )
    (net (code "49") (name "SPI2_CSA") (class "Default")
      (node (ref "X4") (pin "28") (pinfunction "1_28") (pintype "passive"))
      (node (ref "X5") (pin "9") (pinfunction "1_9") (pintype "passive"))
    )
    (net (code "50") (name "SPI2_CSB") (class "Default")
      (node (ref "X4") (pin "27") (pinfunction "1_27") (pintype "passive"))
      (node (ref "X5") (pin "12") (pinfunction "1_12") (pintype "passive"))
    )
    (net (code "51") (name "SPI2_IRQ") (class "Default")
      (node (ref "X4") (pin "25") (pinfunction "1_25") (pintype "passive"))
      (node (ref "X5") (pin "10") (pinfunction "1_10") (pintype "passive"))
    )
    (net (code "52") (name "SPI2_MISO") (class "Default")
      (node (ref "X4") (pin "31") (pinfunction "1_31") (pintype "passive"))
      (node (ref "X5") (pin "14") (pinfunction "1_14") (pintype "passive"))
    )
    (net (code "53") (name "SPI2_MOSI") (class "Default")
      (node (ref "X4") (pin "33") (pinfunction "1_33") (pintype "passive"))
      (node (ref "X5") (pin "15") (pinfunction "1_15") (pintype "passive"))
    )
    (net (code "54") (name "SPI4_CLK") (class "Default")
      (node (ref "X4") (pin "23") (pinfunction "1_23") (pintype "passive"))
      (node (ref "X6") (pin "13") (pinfunction "1_13") (pintype "passive"))
    )
    (net (code "55") (name "SPI4_CSA") (class "Default")
      (node (ref "X4") (pin "22") (pinfunction "1_22") (pintype "passive"))
      (node (ref "X6") (pin "9") (pinfunction "1_9") (pintype "passive"))
    )
    (net (code "56") (name "SPI4_CSB") (class "Default")
      (node (ref "X4") (pin "21") (pinfunction "1_21") (pintype "passive"))
      (node (ref "X6") (pin "12") (pinfunction "1_12") (pintype "passive"))
    )
    (net (code "57") (name "SPI4_CSC") (class "Default")
      (node (ref "X4") (pin "30") (pinfunction "1_30") (pintype "passive"))
    )
    (net (code "58") (name "SPI4_IRQ") (class "Default")
      (node (ref "X4") (pin "19") (pinfunction "1_19") (pintype "passive"))
      (node (ref "X6") (pin "10") (pinfunction "1_10") (pintype "passive"))
    )
    (net (code "59") (name "SPI4_MISO") (class "Default")
      (node (ref "X4") (pin "24") (pinfunction "1_24") (pintype "passive"))
      (node (ref "X6") (pin "14") (pinfunction "1_14") (pintype "passive"))
    )
    (net (code "60") (name "SPI4_MOSI") (class "Default")
      (node (ref "X4") (pin "26") (pinfunction "1_26") (pintype "passive"))
      (node (ref "X6") (pin "15") (pinfunction "1_15") (pintype "passive"))
    )
    (net (code "61") (name "SPI5_CLK") (class "Default")
      (node (ref "X4") (pin "17") (pinfunction "1_17") (pintype "passive"))
      (node (ref "X7") (pin "13") (pinfunction "1_13") (pintype "passive"))
    )
    (net (code "62") (name "SPI5_CSA") (class "Default")
      (node (ref "X4") (pin "11") (pinfunction "1_11") (pintype "passive"))
      (node (ref "X7") (pin "9") (pinfunction "1_9") (pintype "passive"))
    )
    (net (code "63") (name "SPI5_CSB") (class "Default")
      (node (ref "X4") (pin "13") (pinfunction "1_13") (pintype "passive"))
      (node (ref "X7") (pin "12") (pinfunction "1_12") (pintype "passive"))
    )
    (net (code "64") (name "SPI5_CSC") (class "Default")
      (node (ref "X4") (pin "34") (pinfunction "1_34") (pintype "passive"))
    )
    (net (code "65") (name "SPI5_IRQ") (class "Default")
      (node (ref "X4") (pin "9") (pinfunction "1_9") (pintype "passive"))
      (node (ref "X7") (pin "10") (pinfunction "1_10") (pintype "passive"))
    )
    (net (code "66") (name "SPI5_MISO") (class "Default")
      (node (ref "X4") (pin "18") (pinfunction "1_18") (pintype "passive"))
      (node (ref "X7") (pin "14") (pinfunction "1_14") (pintype "passive"))
    )
    (net (code "67") (name "SPI5_MOSI") (class "Default")
      (node (ref "X4") (pin "20") (pinfunction "1_20") (pintype "passive"))
      (node (ref "X7") (pin "15") (pinfunction "1_15") (pintype "passive"))
    )
    (net (code "68") (name "UART_RX") (class "Default")
      (node (ref "X4") (pin "3") (pinfunction "1_3") (pintype "passive"))
      (node (ref "X5") (pin "27") (pinfunction "1_27") (pintype "passive"))
      (node (ref "X6") (pin "27") (pinfunction "1_27") (pintype "passive"))
      (node (ref "X7") (pin "27") (pinfunction "1_27") (pintype "passive"))
    )
    (net (code "69") (name "UART_TX") (class "Default")
      (node (ref "X4") (pin "4") (pinfunction "1_4") (pintype "passive"))
      (node (ref "X5") (pin "28") (pinfunction "1_28") (pintype "passive"))
      (node (ref "X6") (pin "28") (pinfunction "1_28") (pintype "passive"))
      (node (ref "X7") (pin "28") (pinfunction "1_28") (pintype "passive"))
    )
    (net (code "70") (name "unconnected-(IC1-~{INT}-Pad13)") (class "Default")
      (node (ref "IC1") (pin "13") (pinfunction "~{INT}_13") (pintype "output"))
    )
    (net (code "71") (name "unconnected-(K1A-S-Pad12A)") (class "Default")
      (node (ref "K1") (pin "12A") (pinfunction "S_12A") (pintype "passive"))
    )
    (net (code "72") (name "unconnected-(K1B-S-Pad12B)") (class "Default")
      (node (ref "K1") (pin "12B") (pinfunction "S_12B") (pintype "passive"))
    )
    (net (code "73") (name "unconnected-(K2A-S-Pad12A)") (class "Default")
      (node (ref "K2") (pin "12A") (pinfunction "S_12A") (pintype "passive"))
    )
    (net (code "74") (name "unconnected-(X5M-1-Pad20)") (class "Default")
      (node (ref "X5") (pin "20") (pinfunction "1_20") (pintype "passive"))
    )
    (net (code "75") (name "unconnected-(X6M-1-Pad20)") (class "Default")
      (node (ref "X6") (pin "20") (pinfunction "1_20") (pintype "passive"))
    )
    (net (code "76") (name "unconnected-(X7M-1-Pad20)") (class "Default")
      (node (ref "X7") (pin "20") (pinfunction "1_20") (pintype "passive"))
    )
    (net (code "77") (name "~{FAULT}") (class "Default")
      (node (ref "X4") (pin "8") (pinfunction "1_8") (pintype "passive"))
      (node (ref "X5") (pin "3") (pinfunction "1_3") (pintype "passive"))
      (node (ref "X6") (pin "3") (pinfunction "1_3") (pintype "passive"))
      (node (ref "X7") (pin "3") (pinfunction "1_3") (pintype "passive"))
    )
    (net (code "78") (name "~{MRESET}") (class "Default")
      (node (ref "D8") (pin "C") (pinfunction "C_C") (pintype "passive"))
      (node (ref "X4") (pin "6") (pinfunction "1_6") (pintype "passive"))
    )
    (net (code "79") (name "~{RESET}") (class "Default")
      (node (ref "C2") (pin "1") (pinfunction "1_1") (pintype "passive"))
      (node (ref "D7") (pin "A") (pinfunction "A_A") (pintype "passive"))
      (node (ref "D8") (pin "A") (pinfunction "A_A") (pintype "passive"))
      (node (ref "R9") (pin "2") (pinfunction "2_2") (pintype "passive"))
      (node (ref "X5") (pin "4") (pinfunction "1_4") (pintype "passive"))
      (node (ref "X6") (pin "4") (pinfunction "1_4") (pintype "passive"))
      (node (ref "X7") (pin "4") (pinfunction "1_4") (pintype "passive"))
    )
  )
)
